# SerialInterface.net
KiCad netlist of a schematic drawn in Altium Designer
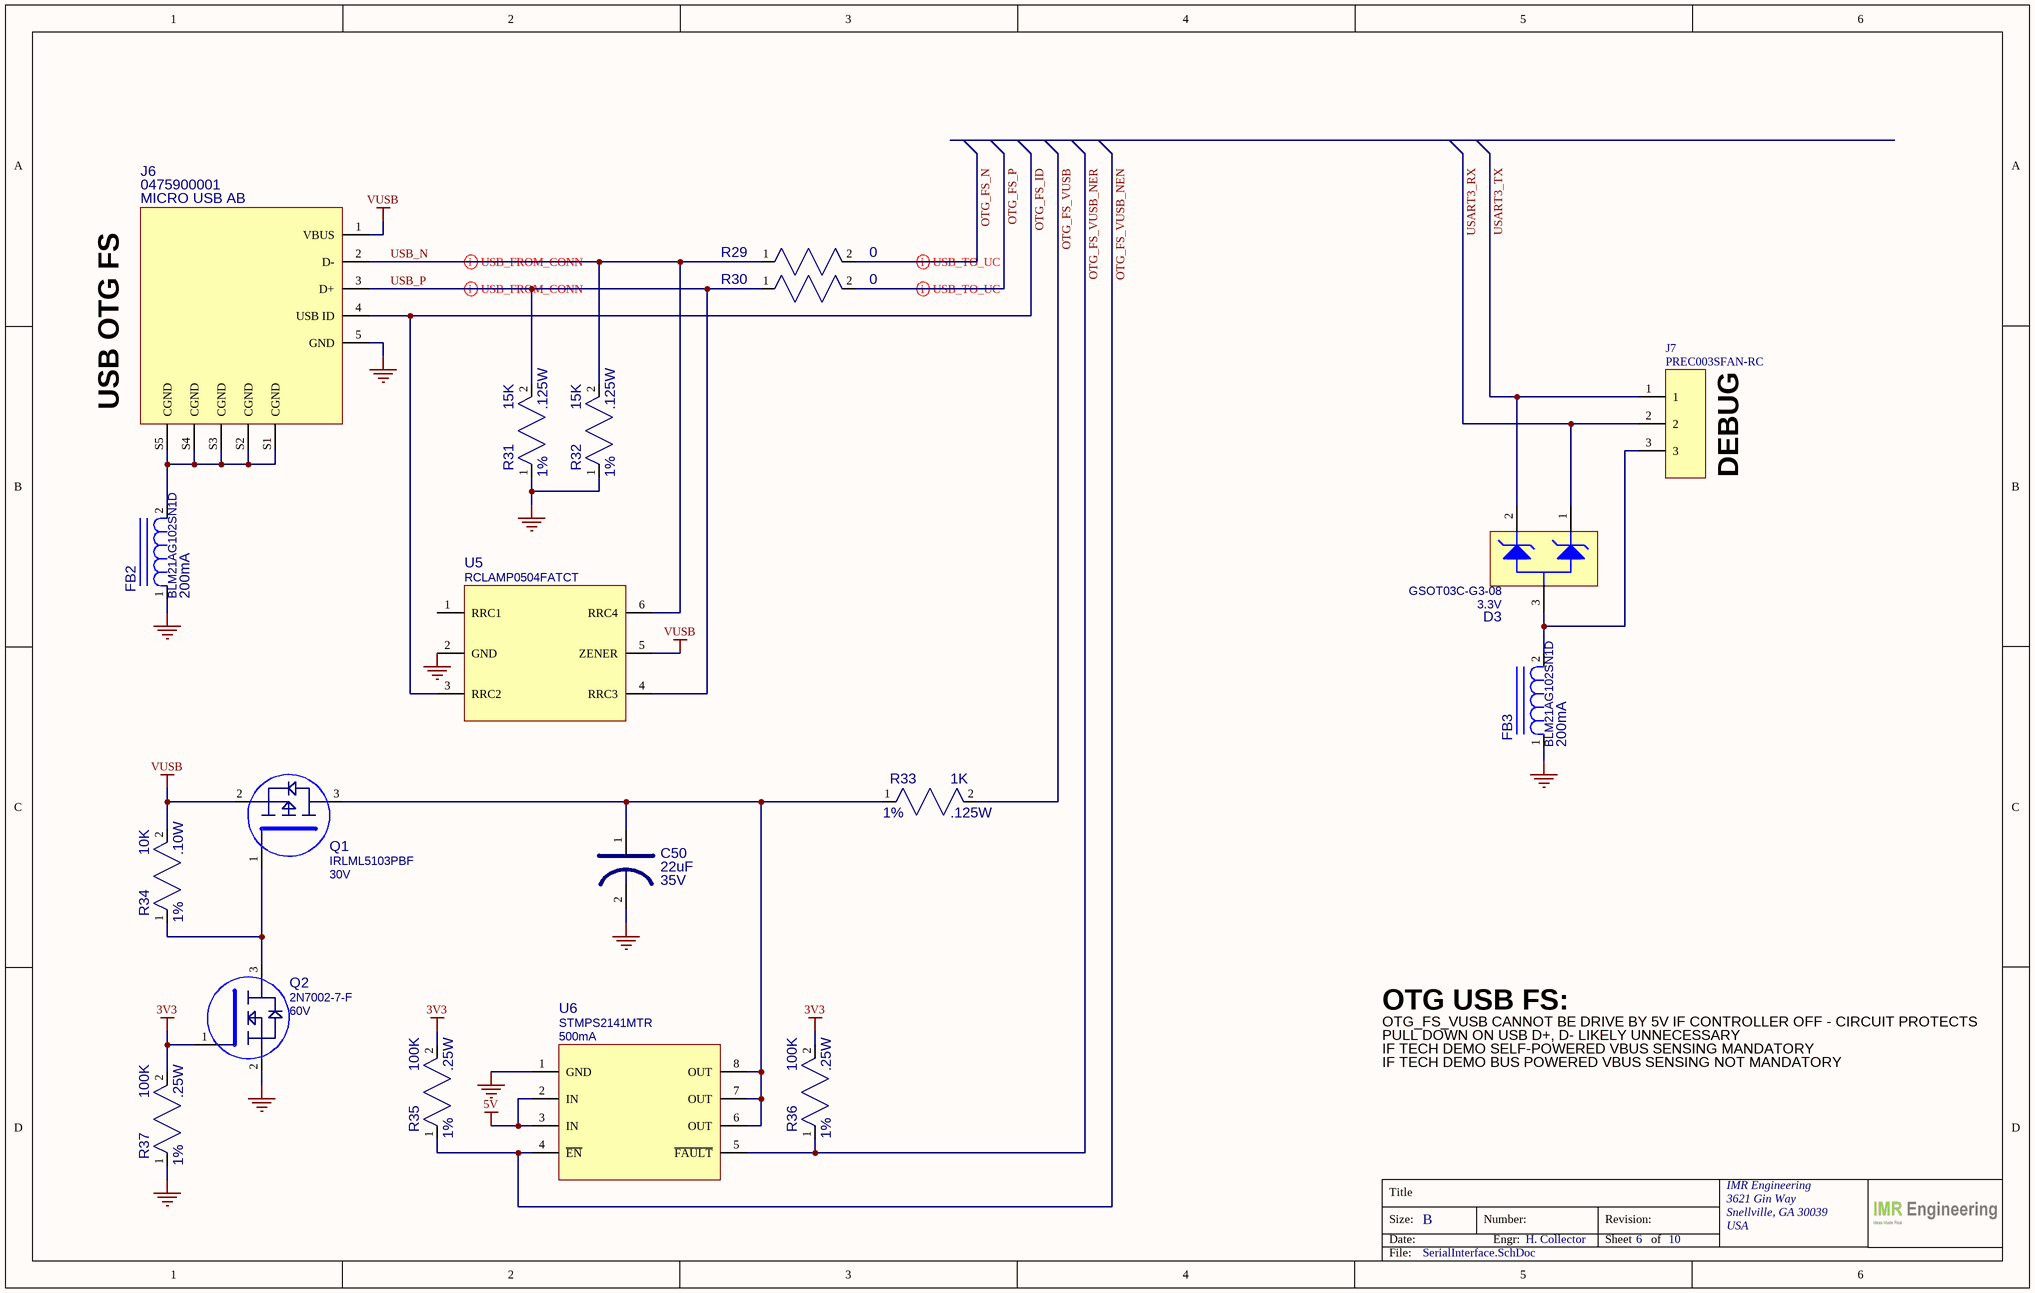
[diagram p0: SerialInterface.SchDoc]

(export (version "E")
  (design (tool "Eeschema 10.0.6"))
  (components
    (comp (ref "C50")
      (value "22uF")
      (footprint "CAP_ALE_SMD_6.6x6.6")
      (description "CAP, AL E, 22UF, 35V, 20%, ROHS")
      (fields (field (name "MFG") "NICHICON") (field (name "TOLERANCE") "20%") (field (name "VOLTAGE") "35V"))
      (libsource (lib "IMR_Lib") (part "CAP_22UF_35V_ALE_NF"))
    )
    (comp (ref "D3")
      (value "3.3V")
      (footprint "SOT-23")
      (description "TVS DIODE 3.3V 12.3V SOT23")
      (fields
        (field (name "MFG") "Vishay Semiconductor")
        (field (name "POWER") "30A (8/20us)")
        (field (name "MFG_PN") "GSOT03C-G3-08")
      )
      (libsource (lib "IMR_Lib") (part "DIODE_TVS_GSOT03C-G3-08"))
    )
    (comp (ref "FB2")
      (value "200mA")
      (footprint "RES_0805")
      (description "FERRITE, 1KOHM AT 100MHZ, 220MA, .450DCR")
      (fields
        (field (name "MFG") "MURATA")
        (field (name "TOLERANCE") "10%")
        (field (name "MFG_PN") "BLM21AG102SN1D")
      )
      (libsource (lib "IMR_Lib") (part "FERRITE_BLM21AG102SN1D"))
    )
    (comp (ref "FB3")
      (value "200mA")
      (footprint "RES_0805")
      (description "FERRITE, 1KOHM AT 100MHZ, 220MA, .450DCR")
      (fields
        (field (name "MFG") "MURATA")
        (field (name "TOLERANCE") "10%")
        (field (name "MFG_PN") "BLM21AG102SN1D")
      )
      (libsource (lib "IMR_Lib") (part "FERRITE_BLM21AG102SN1D"))
    )
    (comp (ref "J6")
      (value "MICRO USB AB")
      (footprint "MICRO_USB_AB_MOLEX_0475900001")
      (description "CONN RCPT MICRO USB AB 5P SMD RA")
      (fields
        (field (name "MFG") "Molex")
        (field (name "MFG_PN") "0475900001")
        (field (name "Comment") "0475900001")
      )
      (libsource (lib "IMR_Lib") (part "CONN_USB_MOLEX_0475900001"))
    )
    (comp (ref "J7")
      (value "PREC003SFAN-RC")
      (footprint "HDR_1X3_100MILL")
      (description "CONN HEADER VERT 3POS 2.54MM")
      (fields (field (name "MFG") "Sullins Connector Solutions"))
      (libsource (lib "IMR_Lib") (part "CONN_3P_SINGLE_ROW"))
    )
    (comp (ref "Q1")
      (value "30V")
      (footprint "SOT-23")
      (description "MOSFET P CHN, VDS=30V, RDSON = .6OHM, SOT 23")
      (fields
        (field (name "MFG_PN") "IRLML5103PBF")
        (field (name "MFG") "INTERNATIONAL RECTIFIER")
        (field (name "Comment") "IRLML5103PBF")
      )
      (libsource (lib "IMR_Lib") (part "MOSFET_PCH_IRLML5103PBF"))
    )
    (comp (ref "Q2")
      (value "60V")
      (footprint "SOT-23")
      (description "MOSFET N-CH 60V 115MA SOT23-3")
      (fields
        (field (name "MFG") "Diodes Incorporated")
        (field (name "MFG_PN") "2N7002-7-F")
        (field (name "Comment") "2N7002-7-F")
      )
      (libsource (lib "IMR_Lib") (part "MOSFET_NCH_2N7002-7-F"))
    )
    (comp (ref "R29")
      (value "0")
      (footprint "PMG_RES_0805")
      (description "RES SMD 0 OHM JUMPER 1/8W 0805")
      (fields (field (name "MFG") "Yageo") (field (name "TOLERANCE") "JUMPER"))
      (libsource (lib "IMR_Lib") (part "RES_0_0805_1/8W"))
    )
    (comp (ref "R30")
      (value "0")
      (footprint "PMG_RES_0805")
      (description "RES SMD 0 OHM JUMPER 1/8W 0805")
      (fields (field (name "MFG") "Yageo") (field (name "TOLERANCE") "JUMPER"))
      (libsource (lib "IMR_Lib") (part "RES_0_0805_1/8W"))
    )
    (comp (ref "R31")
      (value "15K")
      (footprint "RES_0805")
      (description "RES SMD 15K OHM 1% 1/8W 0805")
      (fields
        (field (name "MFG") "Yageo")
        (field (name "TOLERANCE") "1%")
        (field (name "POWER") ".125W")
        (field (name "Comment") "RC0805FR-0715KL")
      )
      (libsource (lib "IMR_Lib") (part "RES_15K_0805_1/8W_1%"))
    )
    (comp (ref "R32")
      (value "15K")
      (footprint "RES_0805")
      (description "RES SMD 15K OHM 1% 1/8W 0805")
      (fields
        (field (name "MFG") "Yageo")
        (field (name "TOLERANCE") "1%")
        (field (name "POWER") ".125W")
        (field (name "Comment") "RC0805FR-0715KL")
      )
      (libsource (lib "IMR_Lib") (part "RES_15K_0805_1/8W_1%"))
    )
    (comp (ref "R33")
      (value "1K")
      (footprint "RES_0805")
      (description "RES SMD 1K OHM 1% 1/8W 0805")
      (fields
        (field (name "MFG") "Yageo")
        (field (name "TOLERANCE") "1%")
        (field (name "POWER") ".125W")
        (field (name "Comment") "RC0805FR-071KL")
      )
      (libsource (lib "IMR_Lib") (part "RES_1K_0805_1/8W_1%"))
    )
    (comp (ref "R34")
      (value "10K")
      (footprint "RES_0603")
      (description "RES SMD 10K OHM 1% 1/10W 0603")
      (fields
        (field (name "MFG") "Yageo")
        (field (name "TOLERANCE") "1%")
        (field (name "POWER") ".10W")
        (field (name "Comment") "RC0603FR-0710KL")
      )
      (libsource (lib "IMR_Lib") (part "RES_10K_0603_1/10W_1%"))
    )
    (comp (ref "R35")
      (value "100K")
      (footprint "PMG_RES_0805")
      (description "RES SMD 100K OHM 1% 1/4W 0805")
      (fields
        (field (name "MFG") "KOA Speer Electronics, Inc.")
        (field (name "TOLERANCE") "1%")
        (field (name "POWER") ".25W")
        (field (name "Comment") "RK73H2ATTD1003F")
      )
      (libsource (lib "IMR_Lib") (part "RES_100K_0805_1/4W_1%"))
    )
    (comp (ref "R36")
      (value "100K")
      (footprint "PMG_RES_0805")
      (description "RES SMD 100K OHM 1% 1/4W 0805")
      (fields
        (field (name "MFG") "KOA Speer Electronics, Inc.")
        (field (name "TOLERANCE") "1%")
        (field (name "POWER") ".25W")
        (field (name "Comment") "RK73H2ATTD1003F")
      )
      (libsource (lib "IMR_Lib") (part "RES_100K_0805_1/4W_1%"))
    )
    (comp (ref "R37")
      (value "100K")
      (footprint "PMG_RES_0805")
      (description "RES SMD 100K OHM 1% 1/4W 0805")
      (fields
        (field (name "MFG") "KOA Speer Electronics, Inc.")
        (field (name "TOLERANCE") "1%")
        (field (name "POWER") ".25W")
        (field (name "Comment") "RK73H2ATTD1003F")
      )
      (libsource (lib "IMR_Lib") (part "RES_100K_0805_1/4W_1%"))
    )
    (comp (ref "U5")
      (value "RCLAMP0504FATCT")
      (footprint "SOT-363_6-TSSOP_SC-88")
      (description "TVS DIODE 5V 25V SC70-6")
      (fields (field (name "MFG") "Semtech Corporation") (field (name "MFG_PN") "RCLAMP0504FATCT"))
      (libsource (lib "IMR_Lib") (part "IC_RCLAMP0504FATCT"))
    )
    (comp (ref "U6")
      (value "500mA")
      (footprint "SO-8")
      (description "IC PWR SWITCH N-CHANNEL 1:1 8SO")
      (fields
        (field (name "MFG") "STMicroelectronics")
        (field (name "MFG_PN") "STMPS2141MTR")
        (field (name "Comment") "STMPS2141MTR")
      )
      (libsource (lib "IMR_Lib") (part "IC_STMPS2141MTR"))
    )
  )
  (nets
    (net (code "1") (name "/OTG_FS_ID") (class "Default")
      (node (ref "J6") (pin "4") (pinfunction "USB_ID_4") (pintype "passive"))
      (node (ref "U5") (pin "3") (pinfunction "RRC2_3") (pintype "passive"))
    )
    (net (code "2") (name "/OTG_FS_N") (class "Default")
      (node (ref "R29") (pin "2") (pinfunction "2_2") (pintype "passive"))
    )
    (net (code "3") (name "/OTG_FS_P") (class "Default")
      (node (ref "R30") (pin "2") (pinfunction "2_2") (pintype "passive"))
    )
    (net (code "4") (name "/OTG_FS_VUSB") (class "Default")
      (node (ref "R33") (pin "2") (pinfunction "2_2") (pintype "passive"))
    )
    (net (code "5") (name "/OTG_FS_VUSB_NEN") (class "Default")
      (node (ref "R35") (pin "1") (pinfunction "1_1") (pintype "passive"))
      (node (ref "U6") (pin "4") (pinfunction "EN_4") (pintype "passive"))
    )
    (net (code "6") (name "/OTG_FS_VUSB_NER") (class "Default")
      (node (ref "R36") (pin "1") (pinfunction "1_1") (pintype "passive"))
      (node (ref "U6") (pin "5") (pinfunction "FAULT_5") (pintype "passive"))
    )
    (net (code "7") (name "/USART3_RX") (class "Default")
      (node (ref "D3") (pin "1") (pinfunction "A1_1") (pintype "passive"))
      (node (ref "J7") (pin "2") (pinfunction "2_2") (pintype "passive"))
    )
    (net (code "8") (name "/USART3_TX") (class "Default")
      (node (ref "D3") (pin "2") (pinfunction "A2_2") (pintype "passive"))
      (node (ref "J7") (pin "1") (pinfunction "1_1") (pintype "passive"))
    )
    (net (code "9") (name "/USB_N") (class "Default")
      (node (ref "J6") (pin "2") (pinfunction "D-_2") (pintype "passive"))
      (node (ref "R29") (pin "1") (pinfunction "1_1") (pintype "passive"))
      (node (ref "R32") (pin "2") (pinfunction "2_2") (pintype "passive"))
      (node (ref "U5") (pin "6") (pinfunction "RRC4_6") (pintype "passive"))
    )
    (net (code "10") (name "/USB_P") (class "Default")
      (node (ref "J6") (pin "3") (pinfunction "D+_3") (pintype "passive"))
      (node (ref "R30") (pin "1") (pinfunction "1_1") (pintype "passive"))
      (node (ref "R31") (pin "2") (pinfunction "2_2") (pintype "passive"))
      (node (ref "U5") (pin "4") (pinfunction "RRC3_4") (pintype "passive"))
    )
    (net (code "11") (name "3V3") (class "Default")
      (node (ref "Q2") (pin "1") (pinfunction "B_1") (pintype "passive"))
      (node (ref "R35") (pin "2") (pinfunction "2_2") (pintype "passive"))
      (node (ref "R36") (pin "2") (pinfunction "2_2") (pintype "passive"))
      (node (ref "R37") (pin "2") (pinfunction "2_2") (pintype "passive"))
    )
    (net (code "12") (name "5V") (class "Default")
      (node (ref "U6") (pin "2") (pinfunction "IN_2") (pintype "passive"))
      (node (ref "U6") (pin "3") (pinfunction "IN_3") (pintype "passive"))
    )
    (net (code "13") (name "GND") (class "Default")
      (node (ref "C50") (pin "2") (pinfunction "2_2") (pintype "passive"))
      (node (ref "FB2") (pin "1") (pinfunction "1_1") (pintype "passive"))
      (node (ref "FB3") (pin "1") (pinfunction "1_1") (pintype "passive"))
      (node (ref "J6") (pin "5") (pinfunction "GND_5") (pintype "passive"))
      (node (ref "Q2") (pin "2") (pinfunction "E_2") (pintype "passive"))
      (node (ref "R31") (pin "1") (pinfunction "1_1") (pintype "passive"))
      (node (ref "R32") (pin "1") (pinfunction "1_1") (pintype "passive"))
      (node (ref "R37") (pin "1") (pinfunction "1_1") (pintype "passive"))
      (node (ref "U5") (pin "2") (pinfunction "GND_2") (pintype "passive"))
      (node (ref "U6") (pin "1") (pinfunction "GND_1") (pintype "passive"))
    )
    (net (code "14") (name "Net-(D3-A)") (class "Default")
      (node (ref "D3") (pin "3") (pinfunction "A_3") (pintype "passive"))
      (node (ref "FB3") (pin "2") (pinfunction "2_2") (pintype "passive"))
      (node (ref "J7") (pin "3") (pinfunction "3_3") (pintype "passive"))
    )
    (net (code "15") (name "Net-(FB2-Pad2)") (class "Default")
      (node (ref "FB2") (pin "2") (pinfunction "2_2") (pintype "passive"))
      (node (ref "J6") (pin "S1") (pinfunction "CGND_S1") (pintype "passive"))
      (node (ref "J6") (pin "S2") (pinfunction "CGND_S2") (pintype "passive"))
      (node (ref "J6") (pin "S3") (pinfunction "CGND_S3") (pintype "passive"))
      (node (ref "J6") (pin "S4") (pinfunction "CGND_S4") (pintype "passive"))
      (node (ref "J6") (pin "S5") (pinfunction "CGND_S5") (pintype "passive"))
    )
    (net (code "16") (name "Net-(Q1-B)") (class "Default")
      (node (ref "Q1") (pin "1") (pinfunction "B_1") (pintype "passive"))
      (node (ref "Q2") (pin "3") (pinfunction "C_3") (pintype "passive"))
      (node (ref "R34") (pin "1") (pinfunction "1_1") (pintype "passive"))
    )
    (net (code "17") (name "Net-(Q1-C)") (class "Default")
      (node (ref "C50") (pin "1") (pinfunction "1_1") (pintype "passive"))
      (node (ref "Q1") (pin "3") (pinfunction "C_3") (pintype "passive"))
      (node (ref "R33") (pin "1") (pinfunction "1_1") (pintype "passive"))
      (node (ref "U6") (pin "6") (pinfunction "OUT_6") (pintype "passive"))
      (node (ref "U6") (pin "7") (pinfunction "OUT_7") (pintype "passive"))
      (node (ref "U6") (pin "8") (pinfunction "OUT_8") (pintype "passive"))
    )
    (net (code "18") (name "VUSB") (class "Default")
      (node (ref "J6") (pin "1") (pinfunction "VBUS_1") (pintype "passive"))
      (node (ref "Q1") (pin "2") (pinfunction "E_2") (pintype "passive"))
      (node (ref "R34") (pin "2") (pinfunction "2_2") (pintype "passive"))
      (node (ref "U5") (pin "5") (pinfunction "ZENER_5") (pintype "passive"))
    )
    (net (code "19") (name "unconnected-(U5-RRC1-Pad1)") (class "Default")
      (node (ref "U5") (pin "1") (pinfunction "RRC1_1") (pintype "passive"))
    )
  )
)
